# template_sensorboard.net
KiCad netlist of a schematic drawn in EAGLE
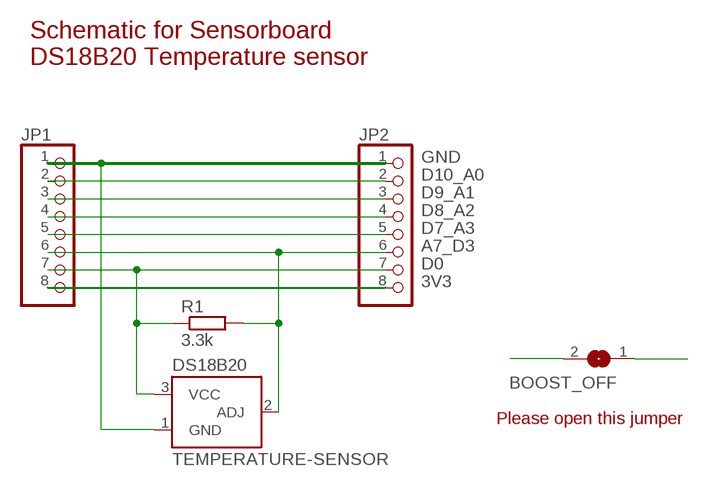
[diagram p0: schematic, sheet 1]

(export (version "E")
  (design (tool "Eeschema 10.0.6"))
  (components
    (comp (ref "BOOST_OFF")
      (value "SJ")
      (footprint "eagle-import:SJ")
      (libsource (lib "eagle-import") (part "SJ"))
    )
    (comp (ref "DS18B20")
      (value "TEMPERATURE-SENSOR")
      (footprint "eagle-import:TO-92")
      (libsource (lib "eagle-import") (part "TEMPERATURE-SENSOR"))
    )
    (comp (ref "JP1")
      (value "PINHD-1X8")
      (footprint "eagle-import:1X08")
      (libsource (lib "eagle-import") (part "PINHD-1X8"))
    )
    (comp (ref "JP2")
      (value "PINHD-1X8")
      (footprint "eagle-import:1X08")
      (libsource (lib "eagle-import") (part "PINHD-1X8"))
    )
    (comp (ref "R1")
      (value "3.3k")
      (footprint "eagle-import:0207_15")
      (libsource (lib "eagle-import") (part "R-EU_0207/15"))
    )
  )
  (nets
    (net (code "1") (name "/3V3") (class "Default")
      (node (ref "JP1") (pin "8") (pinfunction "8_8") (pintype "passive"))
      (node (ref "JP2") (pin "8") (pinfunction "8_8") (pintype "passive"))
    )
    (net (code "2") (name "/A7_D3") (class "Default")
      (node (ref "DS18B20") (pin "2") (pinfunction "ADJ_2") (pintype "bidirectional"))
      (node (ref "JP1") (pin "6") (pinfunction "6_6") (pintype "passive"))
      (node (ref "JP2") (pin "6") (pinfunction "6_6") (pintype "passive"))
      (node (ref "R1") (pin "2") (pinfunction "2_2") (pintype "passive"))
    )
    (net (code "3") (name "/D0") (class "Default")
      (node (ref "DS18B20") (pin "3") (pinfunction "VCC_3") (pintype "bidirectional"))
      (node (ref "JP1") (pin "7") (pinfunction "7_7") (pintype "passive"))
      (node (ref "JP2") (pin "7") (pinfunction "7_7") (pintype "passive"))
      (node (ref "R1") (pin "1") (pinfunction "1_1") (pintype "passive"))
    )
    (net (code "4") (name "/D7_A3") (class "Default")
      (node (ref "JP1") (pin "5") (pinfunction "5_5") (pintype "passive"))
      (node (ref "JP2") (pin "5") (pinfunction "5_5") (pintype "passive"))
    )
    (net (code "5") (name "/D8_A2") (class "Default")
      (node (ref "JP1") (pin "4") (pinfunction "4_4") (pintype "passive"))
      (node (ref "JP2") (pin "4") (pinfunction "4_4") (pintype "passive"))
    )
    (net (code "6") (name "/D9_A1") (class "Default")
      (node (ref "JP1") (pin "3") (pinfunction "3_3") (pintype "passive"))
      (node (ref "JP2") (pin "3") (pinfunction "3_3") (pintype "passive"))
    )
    (net (code "7") (name "/D10_A0") (class "Default")
      (node (ref "JP1") (pin "2") (pinfunction "2_2") (pintype "passive"))
      (node (ref "JP2") (pin "2") (pinfunction "2_2") (pintype "passive"))
    )
    (net (code "8") (name "/GND") (class "Default")
      (node (ref "DS18B20") (pin "1") (pinfunction "GND_1") (pintype "bidirectional"))
      (node (ref "JP1") (pin "1") (pinfunction "1_1") (pintype "passive"))
      (node (ref "JP2") (pin "1") (pinfunction "1_1") (pintype "passive"))
    )
    (net (code "9") (name "unconnected-(BOOST_OFF-Pad1)") (class "Default")
      (node (ref "BOOST_OFF") (pin "1") (pinfunction "1_1") (pintype "passive"))
    )
    (net (code "10") (name "unconnected-(BOOST_OFF-Pad2)") (class "Default")
      (node (ref "BOOST_OFF") (pin "2") (pinfunction "2_2") (pintype "passive"))
    )
  )
)
